# mcu_v041.net
KiCad netlist of a schematic drawn in EAGLE
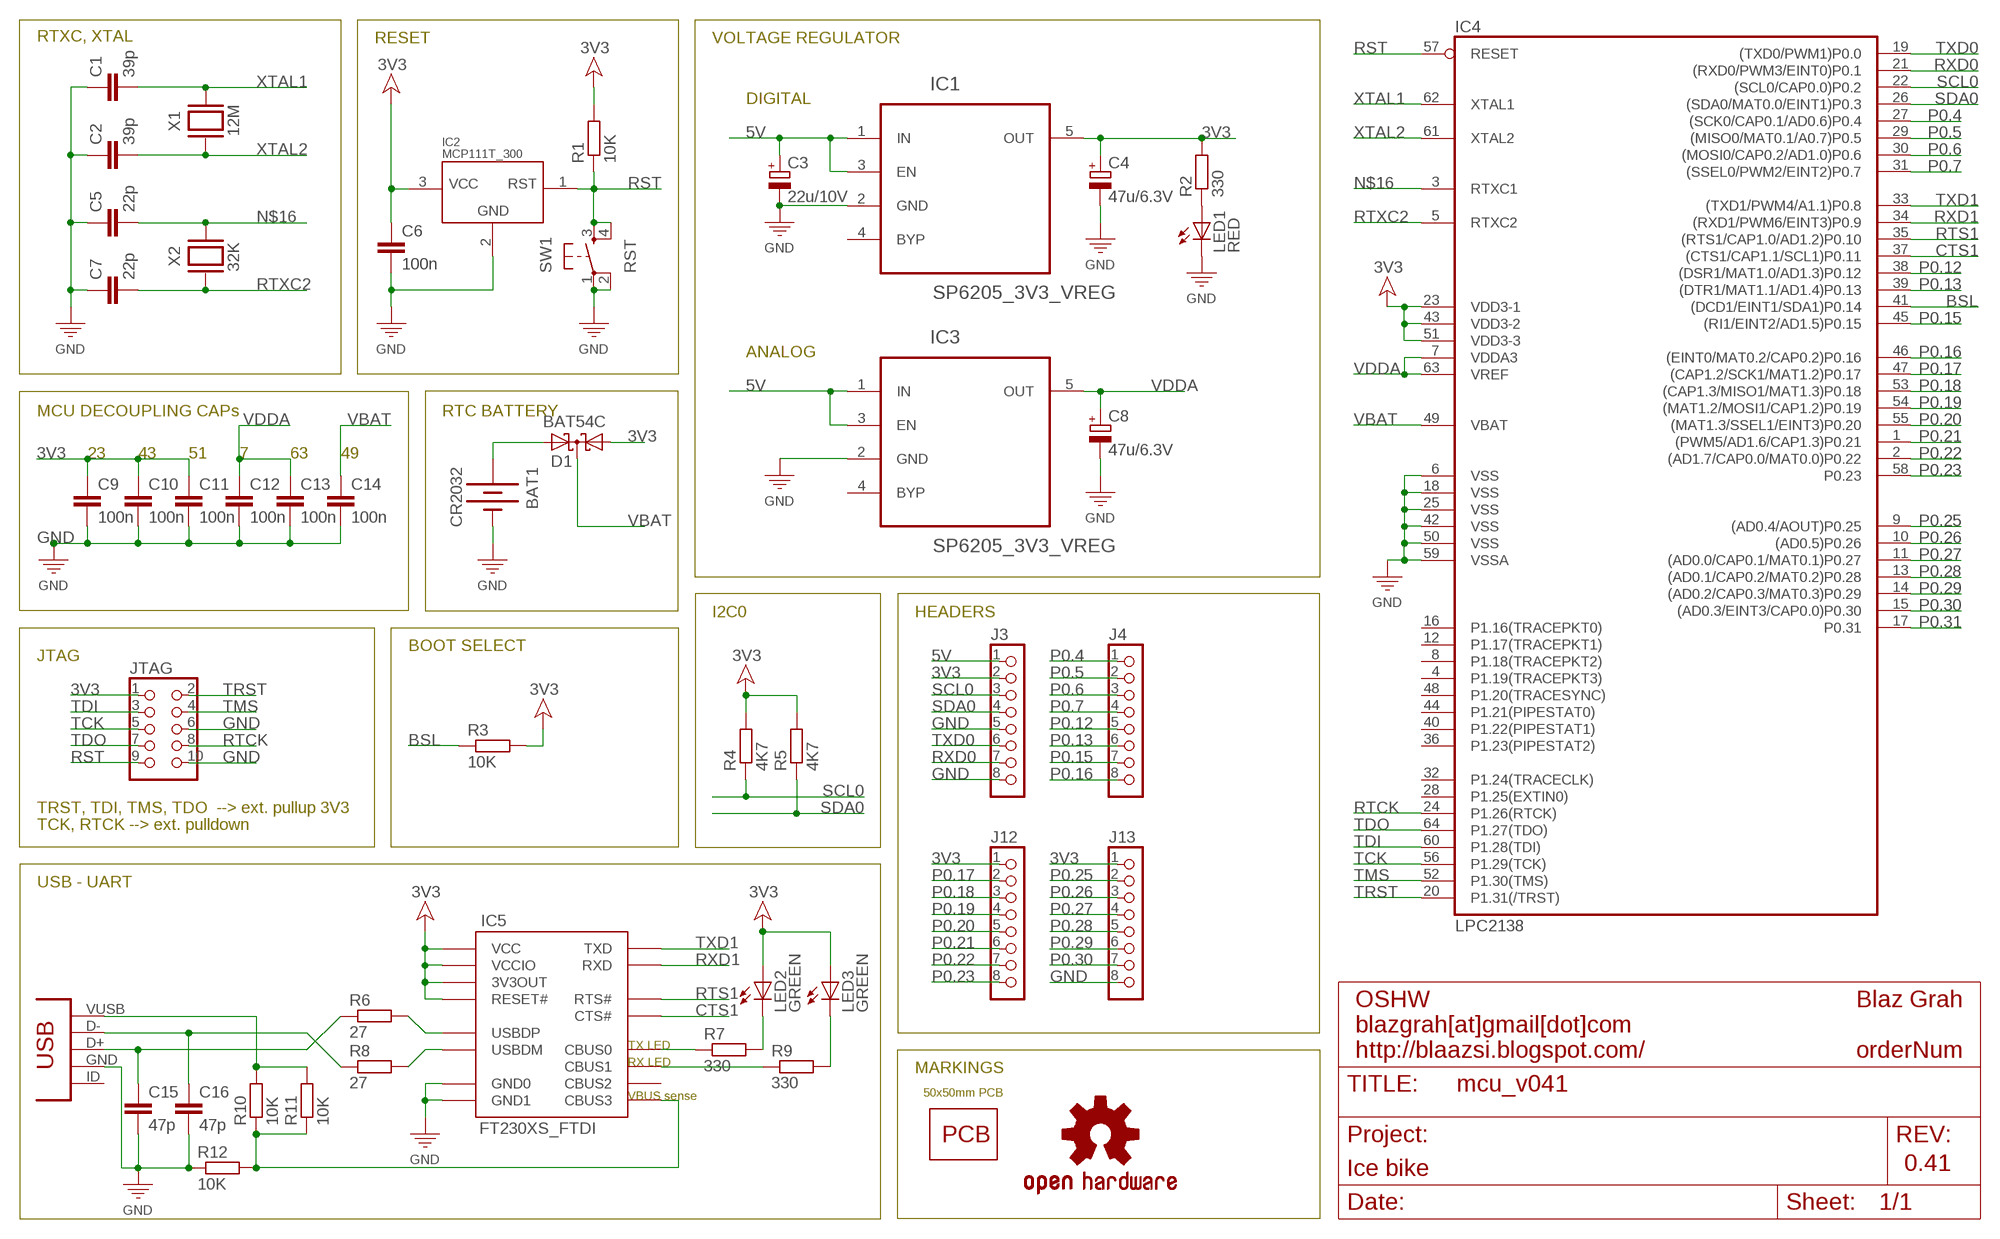
[diagram p0: schematic, sheet 1]

(export (version "E")
  (design (tool "Eeschema 10.0.6"))
  (components
    (comp (ref "BAT1")
      (value "CR2032")
      (footprint "eagle-import:BATTERY_20MM_SMD")
      (libsource (lib "eagle-import") (part "BATTERY20MM"))
    )
    (comp (ref "C1")
      (value "39p")
      (footprint "eagle-import:C0603")
      (libsource (lib "eagle-import") (part "C-EUC0603"))
    )
    (comp (ref "C2")
      (value "39p")
      (footprint "eagle-import:C0603")
      (libsource (lib "eagle-import") (part "C-EUC0603"))
    )
    (comp (ref "C3")
      (value "22u/10V")
      (footprint "eagle-import:SMC_B")
      (libsource (lib "eagle-import") (part "CAPACITOR_POL-SMC_B"))
    )
    (comp (ref "C4")
      (value "47u/6.3V")
      (footprint "eagle-import:SMC_B")
      (libsource (lib "eagle-import") (part "CAPACITOR_POL-SMC_B"))
    )
    (comp (ref "C5")
      (value "22p")
      (footprint "eagle-import:C0603")
      (libsource (lib "eagle-import") (part "C-EUC0603"))
    )
    (comp (ref "C6")
      (value "100n")
      (footprint "eagle-import:C0603")
      (libsource (lib "eagle-import") (part "C-EUC0603"))
    )
    (comp (ref "C7")
      (value "22p")
      (footprint "eagle-import:C0603")
      (libsource (lib "eagle-import") (part "C-EUC0603"))
    )
    (comp (ref "C8")
      (value "47u/6.3V")
      (footprint "eagle-import:SMC_B")
      (libsource (lib "eagle-import") (part "CAPACITOR_POL-SMC_B"))
    )
    (comp (ref "C9")
      (value "100n")
      (footprint "eagle-import:C0603")
      (libsource (lib "eagle-import") (part "C-EUC0603"))
    )
    (comp (ref "C10")
      (value "100n")
      (footprint "eagle-import:C0603")
      (libsource (lib "eagle-import") (part "C-EUC0603"))
    )
    (comp (ref "C11")
      (value "100n")
      (footprint "eagle-import:C0603")
      (libsource (lib "eagle-import") (part "C-EUC0603"))
    )
    (comp (ref "C12")
      (value "100n")
      (footprint "eagle-import:C0603")
      (libsource (lib "eagle-import") (part "C-EUC0603"))
    )
    (comp (ref "C13")
      (value "100n")
      (footprint "eagle-import:C0603")
      (libsource (lib "eagle-import") (part "C-EUC0603"))
    )
    (comp (ref "C14")
      (value "100n")
      (footprint "eagle-import:C0603")
      (libsource (lib "eagle-import") (part "C-EUC0603"))
    )
    (comp (ref "C15")
      (value "47p")
      (footprint "eagle-import:C0603")
      (libsource (lib "eagle-import") (part "C-EUC0603"))
    )
    (comp (ref "C16")
      (value "47p")
      (footprint "eagle-import:C0603")
      (libsource (lib "eagle-import") (part "C-EUC0603"))
    )
    (comp (ref "D1")
      (value "BAT54C")
      (footprint "eagle-import:SOT23")
      (libsource (lib "eagle-import") (part "BAT54C"))
    )
    (comp (ref "DOC")
      (value "FRAME_DINA4_L")
      (footprint "eagle-import:DP_LOGO")
      (fields
        (field (name "AUTHOR") "Blaz Grah")
        (field (name "LICENSE") "OSHW")
        (field (name "PROJECT") "Ice bike")
        (field (name "REV") "0.41")
        (field (name "URL1") "blazgrah[at]gmail[dot]com")
        (field (name "URL2") "http://blaazsi.blogspot.com/")
      )
      (libsource (lib "eagle-import") (part "FRAME_DINA4_L"))
    )
    (comp (ref "IC1")
      (value "SP6205_3V3_VREG")
      (footprint "eagle-import:SOT23-5")
      (libsource (lib "eagle-import") (part "SP6205_3V3_VREG"))
    )
    (comp (ref "IC2")
      (value "MCP111T_300")
      (footprint "eagle-import:SOT23")
      (libsource (lib "eagle-import") (part "MCP111T_300"))
    )
    (comp (ref "IC3")
      (value "SP6205_3V3_VREG")
      (footprint "eagle-import:SOT23-5")
      (libsource (lib "eagle-import") (part "SP6205_3V3_VREG"))
    )
    (comp (ref "IC4")
      (value "LPC2138")
      (footprint "eagle-import:LQFP64")
      (libsource (lib "eagle-import") (part "LCP2138_LQFP64"))
    )
    (comp (ref "IC5")
      (value "FT230XS_FTDI")
      (footprint "eagle-import:SSOP16")
      (libsource (lib "eagle-import") (part "FT230XS_FTDI"))
    )
    (comp (ref "J3")
      (value "CON_HEADER_1X08-PTH")
      (footprint "eagle-import:M1X8")
      (libsource (lib "eagle-import") (part "CON_HEADER_1X08-PTH"))
    )
    (comp (ref "J4")
      (value "CON_HEADER_1X08-PTH")
      (footprint "eagle-import:M1X8")
      (libsource (lib "eagle-import") (part "CON_HEADER_1X08-PTH"))
    )
    (comp (ref "J12")
      (value "CON_HEADER_1X08-PTH")
      (footprint "eagle-import:M1X8")
      (libsource (lib "eagle-import") (part "CON_HEADER_1X08-PTH"))
    )
    (comp (ref "J13")
      (value "CON_HEADER_1X08-PTH")
      (footprint "eagle-import:M1X8")
      (libsource (lib "eagle-import") (part "CON_HEADER_1X08-PTH"))
    )
    (comp (ref "JTAG")
      (value "CON_HEADER_2X05-PTH+SHROUDED_A")
      (footprint "eagle-import:PINSHRD_PTH_2X05")
      (libsource (lib "eagle-import") (part "CON_HEADER_2X05-PTH+SHROUDED_A"))
    )
    (comp (ref "LED1")
      (value "RED")
      (footprint "eagle-import:LED0805")
      (libsource (lib "eagle-import") (part "LED0805"))
    )
    (comp (ref "LED2")
      (value "GREEN")
      (footprint "eagle-import:LED0805")
      (libsource (lib "eagle-import") (part "LED0805"))
    )
    (comp (ref "LED3")
      (value "GREEN")
      (footprint "eagle-import:LED0805")
      (libsource (lib "eagle-import") (part "LED0805"))
    )
    (comp (ref "LOGO1")
      (value "OSHW-LOGOS")
      (footprint "eagle-import:OSHW-LOGO-S")
      (libsource (lib "eagle-import") (part "OSHW-LOGOS"))
    )
    (comp (ref "PCB1")
      (value "PCB")
      (footprint "eagle-import:PCB_50X50")
      (libsource (lib "eagle-import") (part "PCB"))
    )
    (comp (ref "R1")
      (value "10K")
      (footprint "eagle-import:R0603")
      (libsource (lib "eagle-import") (part "R-EU0603"))
    )
    (comp (ref "R2")
      (value "330")
      (footprint "eagle-import:R0603")
      (libsource (lib "eagle-import") (part "R-EU0603"))
    )
    (comp (ref "R3")
      (value "10K")
      (footprint "eagle-import:R0603")
      (libsource (lib "eagle-import") (part "R-EU0603"))
    )
    (comp (ref "R4")
      (value "4K7")
      (footprint "eagle-import:R0603")
      (libsource (lib "eagle-import") (part "R-EU0603"))
    )
    (comp (ref "R5")
      (value "4K7")
      (footprint "eagle-import:R0603")
      (libsource (lib "eagle-import") (part "R-EU0603"))
    )
    (comp (ref "R6")
      (value "27")
      (footprint "eagle-import:R0603")
      (libsource (lib "eagle-import") (part "R-EU0603"))
    )
    (comp (ref "R7")
      (value "330")
      (footprint "eagle-import:R0603")
      (libsource (lib "eagle-import") (part "R-EU0603"))
    )
    (comp (ref "R8")
      (value "27")
      (footprint "eagle-import:R0603")
      (libsource (lib "eagle-import") (part "R-EU0603"))
    )
    (comp (ref "R9")
      (value "330")
      (footprint "eagle-import:R0603")
      (libsource (lib "eagle-import") (part "R-EU0603"))
    )
    (comp (ref "R10")
      (value "10K")
      (footprint "eagle-import:R0603")
      (libsource (lib "eagle-import") (part "R-EU0603"))
    )
    (comp (ref "R11")
      (value "10K")
      (footprint "eagle-import:R0603")
      (libsource (lib "eagle-import") (part "R-EU0603"))
    )
    (comp (ref "R12")
      (value "10K")
      (footprint "eagle-import:R0603")
      (libsource (lib "eagle-import") (part "R-EU0603"))
    )
    (comp (ref "SW1")
      (value "RST")
      (footprint "eagle-import:BUTTON_SW_4P_SMD")
      (libsource (lib "eagle-import") (part "TACTIL_BUTTON"))
    )
    (comp (ref "USB1")
      (value "CON-USB-F-MINI-B")
      (footprint "eagle-import:CONN_USB_MINI-B")
      (libsource (lib "eagle-import") (part "CON-USB-F-MINI-B"))
    )
    (comp (ref "X1")
      (value "12M")
      (footprint "eagle-import:CRYSTAL_12M_4.8X10.6MM")
      (libsource (lib "eagle-import") (part "CRYSTALSMD_4.8X10.6"))
    )
    (comp (ref "X2")
      (value "32K")
      (footprint "eagle-import:CRYSTAL_32K_SMD")
      (libsource (lib "eagle-import") (part "CRYSTALSMD_32K"))
    )
  )
  (nets
    (net (code "1") (name "/5V") (class "Default")
      (node (ref "C3") (pin "+") (pinfunction "+_+") (pintype "passive"))
      (node (ref "IC1") (pin "1") (pinfunction "IN_1") (pintype "input"))
      (node (ref "IC1") (pin "3") (pinfunction "EN_3") (pintype "input"))
      (node (ref "IC3") (pin "1") (pinfunction "IN_1") (pintype "input"))
      (node (ref "IC3") (pin "3") (pinfunction "EN_3") (pintype "input"))
      (node (ref "J3") (pin "1") (pinfunction "1_1") (pintype "passive"))
    )
    (net (code "2") (name "/BSL") (class "Default")
      (node (ref "IC4") (pin "41") (pinfunction "(DCD1/EINT1/SDA1)P0.14_41") (pintype "bidirectional"))
      (node (ref "R3") (pin "1") (pinfunction "1_1") (pintype "passive"))
    )
    (net (code "3") (name "/CTS1") (class "Default")
      (node (ref "IC4") (pin "37") (pinfunction "(CTS1/CAP1.1/SCL1)P0.11_37") (pintype "bidirectional"))
      (node (ref "IC5") (pin "P$6") (pinfunction "CTS#_P$6") (pintype "bidirectional"))
    )
    (net (code "4") (name "/N$16") (class "Default")
      (node (ref "C5") (pin "2") (pinfunction "2_2") (pintype "passive"))
      (node (ref "IC4") (pin "3") (pinfunction "RTXC1_3") (pintype "input"))
      (node (ref "X2") (pin "X2") (pinfunction "2_X2") (pintype "passive"))
    )
    (net (code "5") (name "/P0.4") (class "Default")
      (node (ref "IC4") (pin "27") (pinfunction "(SCK0/CAP0.1/AD0.6)P0.4_27") (pintype "bidirectional"))
      (node (ref "J4") (pin "1") (pinfunction "1_1") (pintype "passive"))
    )
    (net (code "6") (name "/P0.5") (class "Default")
      (node (ref "IC4") (pin "29") (pinfunction "(MISO0/MAT0.1/A0.7)P0.5_29") (pintype "bidirectional"))
      (node (ref "J4") (pin "2") (pinfunction "2_2") (pintype "passive"))
    )
    (net (code "7") (name "/P0.6") (class "Default")
      (node (ref "IC4") (pin "30") (pinfunction "(MOSI0/CAP0.2/AD1.0)P0.6_30") (pintype "bidirectional"))
      (node (ref "J4") (pin "3") (pinfunction "3_3") (pintype "passive"))
    )
    (net (code "8") (name "/P0.7") (class "Default")
      (node (ref "IC4") (pin "31") (pinfunction "(SSEL0/PWM2/EINT2)P0.7_31") (pintype "bidirectional"))
      (node (ref "J4") (pin "4") (pinfunction "4_4") (pintype "passive"))
    )
    (net (code "9") (name "/P0.12") (class "Default")
      (node (ref "IC4") (pin "38") (pinfunction "(DSR1/MAT1.0/AD1.3)P0.12_38") (pintype "bidirectional"))
      (node (ref "J4") (pin "5") (pinfunction "5_5") (pintype "passive"))
    )
    (net (code "10") (name "/P0.13") (class "Default")
      (node (ref "IC4") (pin "39") (pinfunction "(DTR1/MAT1.1/AD1.4)P0.13_39") (pintype "bidirectional"))
      (node (ref "J4") (pin "6") (pinfunction "6_6") (pintype "passive"))
    )
    (net (code "11") (name "/P0.15") (class "Default")
      (node (ref "IC4") (pin "45") (pinfunction "(RI1/EINT2/AD1.5)P0.15_45") (pintype "bidirectional"))
      (node (ref "J4") (pin "7") (pinfunction "7_7") (pintype "passive"))
    )
    (net (code "12") (name "/P0.16") (class "Default")
      (node (ref "IC4") (pin "46") (pinfunction "(EINT0/MAT0.2/CAP0.2)P0.16_46") (pintype "bidirectional"))
      (node (ref "J4") (pin "8") (pinfunction "8_8") (pintype "passive"))
    )
    (net (code "13") (name "/P0.17") (class "Default")
      (node (ref "IC4") (pin "47") (pinfunction "(CAP1.2/SCK1/MAT1.2)P0.17_47") (pintype "bidirectional"))
      (node (ref "J12") (pin "2") (pinfunction "2_2") (pintype "passive"))
    )
    (net (code "14") (name "/P0.18") (class "Default")
      (node (ref "IC4") (pin "53") (pinfunction "(CAP1.3/MISO1/MAT1.3)P0.18_53") (pintype "bidirectional"))
      (node (ref "J12") (pin "3") (pinfunction "3_3") (pintype "passive"))
    )
    (net (code "15") (name "/P0.19") (class "Default")
      (node (ref "IC4") (pin "54") (pinfunction "(MAT1.2/MOSI1/CAP1.2)P0.19_54") (pintype "bidirectional"))
      (node (ref "J12") (pin "4") (pinfunction "4_4") (pintype "passive"))
    )
    (net (code "16") (name "/P0.20") (class "Default")
      (node (ref "IC4") (pin "55") (pinfunction "(MAT1.3/SSEL1/EINT3)P0.20_55") (pintype "bidirectional"))
      (node (ref "J12") (pin "5") (pinfunction "5_5") (pintype "passive"))
    )
    (net (code "17") (name "/P0.21") (class "Default")
      (node (ref "IC4") (pin "1") (pinfunction "(PWM5/AD1.6/CAP1.3)P0.21_1") (pintype "bidirectional"))
      (node (ref "J12") (pin "6") (pinfunction "6_6") (pintype "passive"))
    )
    (net (code "18") (name "/P0.22") (class "Default")
      (node (ref "IC4") (pin "2") (pinfunction "(AD1.7/CAP0.0/MAT0.0)P0.22_2") (pintype "bidirectional"))
      (node (ref "J12") (pin "7") (pinfunction "7_7") (pintype "passive"))
    )
    (net (code "19") (name "/P0.23") (class "Default")
      (node (ref "IC4") (pin "58") (pinfunction "P0.23_58") (pintype "bidirectional"))
      (node (ref "J12") (pin "8") (pinfunction "8_8") (pintype "passive"))
    )
    (net (code "20") (name "/P0.25") (class "Default")
      (node (ref "IC4") (pin "9") (pinfunction "(AD0.4/AOUT)P0.25_9") (pintype "bidirectional"))
      (node (ref "J13") (pin "2") (pinfunction "2_2") (pintype "passive"))
    )
    (net (code "21") (name "/P0.26") (class "Default")
      (node (ref "IC4") (pin "10") (pinfunction "(AD0.5)P0.26_10") (pintype "bidirectional"))
      (node (ref "J13") (pin "3") (pinfunction "3_3") (pintype "passive"))
    )
    (net (code "22") (name "/P0.27") (class "Default")
      (node (ref "IC4") (pin "11") (pinfunction "(AD0.0/CAP0.1/MAT0.1)P0.27_11") (pintype "bidirectional"))
      (node (ref "J13") (pin "4") (pinfunction "4_4") (pintype "passive"))
    )
    (net (code "23") (name "/P0.28") (class "Default")
      (node (ref "IC4") (pin "13") (pinfunction "(AD0.1/CAP0.2/MAT0.2)P0.28_13") (pintype "bidirectional"))
      (node (ref "J13") (pin "5") (pinfunction "5_5") (pintype "passive"))
    )
    (net (code "24") (name "/P0.29") (class "Default")
      (node (ref "IC4") (pin "14") (pinfunction "(AD0.2/CAP0.3/MAT0.3)P0.29_14") (pintype "bidirectional"))
      (node (ref "J13") (pin "6") (pinfunction "6_6") (pintype "passive"))
    )
    (net (code "25") (name "/P0.30") (class "Default")
      (node (ref "IC4") (pin "15") (pinfunction "(AD0.3/EINT3/CAP0.0)P0.30_15") (pintype "bidirectional"))
      (node (ref "J13") (pin "7") (pinfunction "7_7") (pintype "passive"))
    )
    (net (code "26") (name "/P0.31") (class "Default")
      (node (ref "IC4") (pin "17") (pinfunction "P0.31_17") (pintype "output"))
    )
    (net (code "27") (name "/RST") (class "Default")
      (node (ref "IC2") (pin "1") (pinfunction "RST_1") (pintype "output"))
      (node (ref "IC4") (pin "57") (pinfunction "RESET_57") (pintype "input"))
      (node (ref "JTAG") (pin "9") (pinfunction "9_9") (pintype "passive"))
      (node (ref "R1") (pin "1") (pinfunction "1_1") (pintype "passive"))
      (node (ref "SW1") (pin "3") (pinfunction "3_3") (pintype "passive"))
      (node (ref "SW1") (pin "4") (pinfunction "4_4") (pintype "passive"))
    )
    (net (code "28") (name "/RTCK") (class "Default")
      (node (ref "IC4") (pin "24") (pinfunction "P1.26(RTCK)_24") (pintype "bidirectional"))
      (node (ref "JTAG") (pin "8") (pinfunction "8_8") (pintype "passive"))
    )
    (net (code "29") (name "/RTS1") (class "Default")
      (node (ref "IC4") (pin "35") (pinfunction "(RTS1/CAP1.0/AD1.2)P0.10_35") (pintype "bidirectional"))
      (node (ref "IC5") (pin "P$2") (pinfunction "RTS#_P$2") (pintype "bidirectional"))
    )
    (net (code "30") (name "/RTXC2") (class "Default")
      (node (ref "C7") (pin "2") (pinfunction "2_2") (pintype "passive"))
      (node (ref "IC4") (pin "5") (pinfunction "RTXC2_5") (pintype "output"))
      (node (ref "X2") (pin "X1") (pinfunction "1_X1") (pintype "passive"))
    )
    (net (code "31") (name "/RXD0") (class "Default")
      (node (ref "IC4") (pin "21") (pinfunction "(RXD0/PWM3/EINT0)P0.1_21") (pintype "bidirectional"))
      (node (ref "J3") (pin "7") (pinfunction "7_7") (pintype "passive"))
    )
    (net (code "32") (name "/RXD1") (class "Default")
      (node (ref "IC4") (pin "34") (pinfunction "(RXD1/PWM6/EINT3)P0.9_34") (pintype "bidirectional"))
      (node (ref "IC5") (pin "P$4") (pinfunction "RXD_P$4") (pintype "bidirectional"))
    )
    (net (code "33") (name "/SCL0") (class "Default")
      (node (ref "IC4") (pin "22") (pinfunction "(SCL0/CAP0.0)P0.2_22") (pintype "bidirectional"))
      (node (ref "J3") (pin "3") (pinfunction "3_3") (pintype "passive"))
      (node (ref "R4") (pin "1") (pinfunction "1_1") (pintype "passive"))
    )
    (net (code "34") (name "/SDA0") (class "Default")
      (node (ref "IC4") (pin "26") (pinfunction "(SDA0/MAT0.0/EINT1)P0.3_26") (pintype "bidirectional"))
      (node (ref "J3") (pin "4") (pinfunction "4_4") (pintype "passive"))
      (node (ref "R5") (pin "1") (pinfunction "1_1") (pintype "passive"))
    )
    (net (code "35") (name "/TCK") (class "Default")
      (node (ref "IC4") (pin "56") (pinfunction "P1.29(TCK)_56") (pintype "bidirectional"))
      (node (ref "JTAG") (pin "5") (pinfunction "5_5") (pintype "passive"))
    )
    (net (code "36") (name "/TDI") (class "Default")
      (node (ref "IC4") (pin "60") (pinfunction "P1.28(TDI)_60") (pintype "bidirectional"))
      (node (ref "JTAG") (pin "3") (pinfunction "3_3") (pintype "passive"))
    )
    (net (code "37") (name "/TDO") (class "Default")
      (node (ref "IC4") (pin "64") (pinfunction "P1.27(TDO)_64") (pintype "bidirectional"))
      (node (ref "JTAG") (pin "7") (pinfunction "7_7") (pintype "passive"))
    )
    (net (code "38") (name "/TMS") (class "Default")
      (node (ref "IC4") (pin "52") (pinfunction "P1.30(TMS)_52") (pintype "bidirectional"))
      (node (ref "JTAG") (pin "4") (pinfunction "4_4") (pintype "passive"))
    )
    (net (code "39") (name "/TRST") (class "Default")
      (node (ref "IC4") (pin "20") (pinfunction "P1.31(/TRST)_20") (pintype "bidirectional"))
      (node (ref "JTAG") (pin "2") (pinfunction "2_2") (pintype "passive"))
    )
    (net (code "40") (name "/TXD0") (class "Default")
      (node (ref "IC4") (pin "19") (pinfunction "(TXD0/PWM1)P0.0_19") (pintype "bidirectional"))
      (node (ref "J3") (pin "6") (pinfunction "6_6") (pintype "passive"))
    )
    (net (code "41") (name "/TXD1") (class "Default")
      (node (ref "IC4") (pin "33") (pinfunction "(TXD1/PWM4/A1.1)P0.8_33") (pintype "bidirectional"))
      (node (ref "IC5") (pin "P$1") (pinfunction "TXD_P$1") (pintype "bidirectional"))
    )
    (net (code "42") (name "/VBAT") (class "Default")
      (node (ref "C14") (pin "1") (pinfunction "1_1") (pintype "passive"))
      (node (ref "D1") (pin "3") (pinfunction "CC_3") (pintype "passive"))
      (node (ref "IC4") (pin "49") (pinfunction "VBAT_49") (pintype "power_in"))
    )
    (net (code "43") (name "/VDDA") (class "Default")
      (node (ref "C12") (pin "1") (pinfunction "1_1") (pintype "passive"))
      (node (ref "C13") (pin "1") (pinfunction "1_1") (pintype "passive"))
      (node (ref "C8") (pin "+") (pinfunction "+_+") (pintype "passive"))
      (node (ref "IC3") (pin "5") (pinfunction "OUT_5") (pintype "power_in"))
      (node (ref "IC4") (pin "63") (pinfunction "VREF_63") (pintype "input"))
      (node (ref "IC4") (pin "7") (pinfunction "VDDA3_7") (pintype "power_in"))
    )
    (net (code "44") (name "/XTAL1") (class "Default")
      (node (ref "C1") (pin "2") (pinfunction "2_2") (pintype "passive"))
      (node (ref "IC4") (pin "62") (pinfunction "XTAL1_62") (pintype "input"))
      (node (ref "X1") (pin "P$2") (pinfunction "2_P$2") (pintype "passive"))
    )
    (net (code "45") (name "/XTAL2") (class "Default")
      (node (ref "C2") (pin "2") (pinfunction "2_2") (pintype "passive"))
      (node (ref "IC4") (pin "61") (pinfunction "XTAL2_61") (pintype "output"))
      (node (ref "X1") (pin "P$1") (pinfunction "1_P$1") (pintype "passive"))
    )
    (net (code "46") (name "3V3") (class "Default")
      (node (ref "C10") (pin "1") (pinfunction "1_1") (pintype "passive"))
      (node (ref "C11") (pin "1") (pinfunction "1_1") (pintype "passive"))
      (node (ref "C4") (pin "+") (pinfunction "+_+") (pintype "passive"))
      (node (ref "C6") (pin "1") (pinfunction "1_1") (pintype "passive"))
      (node (ref "C9") (pin "1") (pinfunction "1_1") (pintype "passive"))
      (node (ref "D1") (pin "1") (pinfunction "A1_1") (pintype "passive"))
      (node (ref "IC1") (pin "5") (pinfunction "OUT_5") (pintype "power_in"))
      (node (ref "IC2") (pin "3") (pinfunction "VCC_3") (pintype "input"))
      (node (ref "IC4") (pin "23") (pinfunction "VDD3-1_23") (pintype "power_in"))
      (node (ref "IC4") (pin "43") (pinfunction "VDD3-2_43") (pintype "power_in"))
      (node (ref "IC4") (pin "51") (pinfunction "VDD3-3_51") (pintype "power_in"))
      (node (ref "IC5") (pin "P$10") (pinfunction "3V3OUT_P$10") (pintype "power_in"))
      (node (ref "IC5") (pin "P$11") (pinfunction "RESET#_P$11") (pintype "bidirectional"))
      (node (ref "IC5") (pin "P$12") (pinfunction "VCC_P$12") (pintype "power_in"))
      (node (ref "IC5") (pin "P$3") (pinfunction "VCCIO_P$3") (pintype "power_in"))
      (node (ref "J12") (pin "1") (pinfunction "1_1") (pintype "passive"))
      (node (ref "J13") (pin "1") (pinfunction "1_1") (pintype "passive"))
      (node (ref "J3") (pin "2") (pinfunction "2_2") (pintype "passive"))
      (node (ref "JTAG") (pin "1") (pinfunction "1_1") (pintype "passive"))
      (node (ref "LED2") (pin "A") (pinfunction "A_A") (pintype "passive"))
      (node (ref "LED3") (pin "A") (pinfunction "A_A") (pintype "passive"))
      (node (ref "R1") (pin "2") (pinfunction "2_2") (pintype "passive"))
      (node (ref "R2") (pin "2") (pinfunction "2_2") (pintype "passive"))
      (node (ref "R3") (pin "2") (pinfunction "2_2") (pintype "passive"))
      (node (ref "R4") (pin "2") (pinfunction "2_2") (pintype "passive"))
      (node (ref "R5") (pin "2") (pinfunction "2_2") (pintype "passive"))
    )
    (net (code "47") (name "GND") (class "Default")
      (node (ref "BAT1") (pin "NEG") (pinfunction "NEG_NEG") (pintype "power_in"))
      (node (ref "C1") (pin "1") (pinfunction "1_1") (pintype "passive"))
      (node (ref "C10") (pin "2") (pinfunction "2_2") (pintype "passive"))
      (node (ref "C11") (pin "2") (pinfunction "2_2") (pintype "passive"))
      (node (ref "C12") (pin "2") (pinfunction "2_2") (pintype "passive"))
      (node (ref "C13") (pin "2") (pinfunction "2_2") (pintype "passive"))
      (node (ref "C14") (pin "2") (pinfunction "2_2") (pintype "passive"))
      (node (ref "C15") (pin "2") (pinfunction "2_2") (pintype "passive"))
      (node (ref "C16") (pin "2") (pinfunction "2_2") (pintype "passive"))
      (node (ref "C2") (pin "1") (pinfunction "1_1") (pintype "passive"))
      (node (ref "C3") (pin "-") (pinfunction "-_-") (pintype "passive"))
      (node (ref "C4") (pin "-") (pinfunction "-_-") (pintype "passive"))
      (node (ref "C5") (pin "1") (pinfunction "1_1") (pintype "passive"))
      (node (ref "C6") (pin "2") (pinfunction "2_2") (pintype "passive"))
      (node (ref "C7") (pin "1") (pinfunction "1_1") (pintype "passive"))
      (node (ref "C8") (pin "-") (pinfunction "-_-") (pintype "passive"))
      (node (ref "C9") (pin "2") (pinfunction "2_2") (pintype "passive"))
      (node (ref "IC1") (pin "2") (pinfunction "GND_2") (pintype "power_in"))
      (node (ref "IC2") (pin "2") (pinfunction "GND_2") (pintype "power_in"))
      (node (ref "IC3") (pin "2") (pinfunction "GND_2") (pintype "power_in"))
      (node (ref "IC4") (pin "18") (pinfunction "VSS_18") (pintype "power_in"))
      (node (ref "IC4") (pin "25") (pinfunction "VSS_25") (pintype "power_in"))
      (node (ref "IC4") (pin "42") (pinfunction "VSS_42") (pintype "power_in"))
      (node (ref "IC4") (pin "50") (pinfunction "VSS_50") (pintype "power_in"))
      (node (ref "IC4") (pin "59") (pinfunction "VSSA_59") (pintype "power_in"))
      (node (ref "IC4") (pin "6") (pinfunction "VSS_6") (pintype "power_in"))
      (node (ref "IC5") (pin "P$13") (pinfunction "GND1_P$13") (pintype "power_in"))
      (node (ref "IC5") (pin "P$5") (pinfunction "GND0_P$5") (pintype "power_in"))
      (node (ref "J13") (pin "8") (pinfunction "8_8") (pintype "passive"))
      (node (ref "J3") (pin "5") (pinfunction "5_5") (pintype "passive"))
      (node (ref "J3") (pin "8") (pinfunction "8_8") (pintype "passive"))
      (node (ref "JTAG") (pin "10") (pinfunction "10_10") (pintype "passive"))
      (node (ref "JTAG") (pin "6") (pinfunction "6_6") (pintype "passive"))
      (node (ref "LED1") (pin "C") (pinfunction "C_C") (pintype "passive"))
      (node (ref "R12") (pin "1") (pinfunction "1_1") (pintype "passive"))
      (node (ref "SW1") (pin "1") (pinfunction "1_1") (pintype "passive"))
      (node (ref "SW1") (pin "2") (pinfunction "2_2") (pintype "passive"))
      (node (ref "USB1") (pin "GND") (pinfunction "GND_GND") (pintype "bidirectional"))
    )
    (net (code "48") (name "Net-(C15-Pad1)") (class "Default")
      (node (ref "C15") (pin "1") (pinfunction "1_1") (pintype "passive"))
      (node (ref "R6") (pin "1") (pinfunction "1_1") (pintype "passive"))
      (node (ref "USB1") (pin "D+") (pinfunction "D+_D+") (pintype "bidirectional"))
    )
    (net (code "49") (name "Net-(C16-Pad1)") (class "Default")
      (node (ref "C16") (pin "1") (pinfunction "1_1") (pintype "passive"))
      (node (ref "R8") (pin "1") (pinfunction "1_1") (pintype "passive"))
      (node (ref "USB1") (pin "D-") (pinfunction "D-_D-") (pintype "bidirectional"))
    )
    (net (code "50") (name "Net-(D1-A2)") (class "Default")
      (node (ref "BAT1") (pin "POS1") (pinfunction "POZ_POS1") (pintype "power_in"))
      (node (ref "BAT1") (pin "POS2") (pinfunction "POZ_POS2") (pintype "power_in"))
      (node (ref "D1") (pin "2") (pinfunction "A2_2") (pintype "passive"))
    )
    (net (code "51") (name "Net-(IC5-CBUS0)") (class "Default")
      (node (ref "IC5") (pin "P$15") (pinfunction "CBUS0_P$15") (pintype "bidirectional"))
      (node (ref "R7") (pin "1") (pinfunction "1_1") (pintype "passive"))
    )
    (net (code "52") (name "Net-(IC5-CBUS1)") (class "Default")
      (node (ref "IC5") (pin "P$14") (pinfunction "CBUS1_P$14") (pintype "bidirectional"))
      (node (ref "R9") (pin "1") (pinfunction "1_1") (pintype "passive"))
    )
    (net (code "53") (name "Net-(IC5-CBUS3)") (class "Default")
      (node (ref "IC5") (pin "P$16") (pinfunction "CBUS3_P$16") (pintype "bidirectional"))
      (node (ref "R10") (pin "1") (pinfunction "1_1") (pintype "passive"))
      (node (ref "R11") (pin "1") (pinfunction "1_1") (pintype "passive"))
      (node (ref "R12") (pin "2") (pinfunction "2_2") (pintype "passive"))
    )
    (net (code "54") (name "Net-(IC5-USBDM)") (class "Default")
      (node (ref "IC5") (pin "P$9") (pinfunction "USBDM_P$9") (pintype "bidirectional"))
      (node (ref "R8") (pin "2") (pinfunction "2_2") (pintype "passive"))
    )
    (net (code "55") (name "Net-(IC5-USBDP)") (class "Default")
      (node (ref "IC5") (pin "P$8") (pinfunction "USBDP_P$8") (pintype "bidirectional"))
      (node (ref "R6") (pin "2") (pinfunction "2_2") (pintype "passive"))
    )
    (net (code "56") (name "Net-(LED1-PadA)") (class "Default")
      (node (ref "LED1") (pin "A") (pinfunction "A_A") (pintype "passive"))
      (node (ref "R2") (pin "1") (pinfunction "1_1") (pintype "passive"))
    )
    (net (code "57") (name "Net-(LED2-PadC)") (class "Default")
      (node (ref "LED2") (pin "C") (pinfunction "C_C") (pintype "passive"))
      (node (ref "R7") (pin "2") (pinfunction "2_2") (pintype "passive"))
    )
    (net (code "58") (name "Net-(LED3-PadC)") (class "Default")
      (node (ref "LED3") (pin "C") (pinfunction "C_C") (pintype "passive"))
      (node (ref "R9") (pin "2") (pinfunction "2_2") (pintype "passive"))
    )
    (net (code "59") (name "Net-(R10-Pad2)") (class "Default")
      (node (ref "R10") (pin "2") (pinfunction "2_2") (pintype "passive"))
      (node (ref "R11") (pin "2") (pinfunction "2_2") (pintype "passive"))
      (node (ref "USB1") (pin "VUSB") (pinfunction "VUSB_VUSB") (pintype "bidirectional"))
    )
    (net (code "60") (name "unconnected-(IC1-BYP-Pad4)") (class "Default")
      (node (ref "IC1") (pin "4") (pinfunction "BYP_4") (pintype "no_connect"))
    )
    (net (code "61") (name "unconnected-(IC3-BYP-Pad4)") (class "Default")
      (node (ref "IC3") (pin "4") (pinfunction "BYP_4") (pintype "no_connect"))
    )
    (net (code "62") (name "unconnected-(IC4-P1.16(TRACEPKT0)-Pad16)") (class "Default")
      (node (ref "IC4") (pin "16") (pinfunction "P1.16(TRACEPKT0)_16") (pintype "bidirectional"))
    )
    (net (code "63") (name "unconnected-(IC4-P1.17(TRACEPKT1)-Pad12)") (class "Default")
      (node (ref "IC4") (pin "12") (pinfunction "P1.17(TRACEPKT1)_12") (pintype "bidirectional"))
    )
    (net (code "64") (name "unconnected-(IC4-P1.18(TRACEPKT2)-Pad8)") (class "Default")
      (node (ref "IC4") (pin "8") (pinfunction "P1.18(TRACEPKT2)_8") (pintype "bidirectional"))
    )
    (net (code "65") (name "unconnected-(IC4-P1.19(TRACEPKT3)-Pad4)") (class "Default")
      (node (ref "IC4") (pin "4") (pinfunction "P1.19(TRACEPKT3)_4") (pintype "bidirectional"))
    )
    (net (code "66") (name "unconnected-(IC4-P1.20(TRACESYNC)-Pad48)") (class "Default")
      (node (ref "IC4") (pin "48") (pinfunction "P1.20(TRACESYNC)_48") (pintype "bidirectional"))
    )
    (net (code "67") (name "unconnected-(IC4-P1.21(PIPESTAT0)-Pad44)") (class "Default")
      (node (ref "IC4") (pin "44") (pinfunction "P1.21(PIPESTAT0)_44") (pintype "bidirectional"))
    )
    (net (code "68") (name "unconnected-(IC4-P1.22(PIPESTAT1)-Pad40)") (class "Default")
      (node (ref "IC4") (pin "40") (pinfunction "P1.22(PIPESTAT1)_40") (pintype "bidirectional"))
    )
    (net (code "69") (name "unconnected-(IC4-P1.23(PIPESTAT2)-Pad36)") (class "Default")
      (node (ref "IC4") (pin "36") (pinfunction "P1.23(PIPESTAT2)_36") (pintype "bidirectional"))
    )
    (net (code "70") (name "unconnected-(IC4-P1.24(TRACECLK)-Pad32)") (class "Default")
      (node (ref "IC4") (pin "32") (pinfunction "P1.24(TRACECLK)_32") (pintype "bidirectional"))
    )
    (net (code "71") (name "unconnected-(IC4-P1.25(EXTIN0)-Pad28)") (class "Default")
      (node (ref "IC4") (pin "28") (pinfunction "P1.25(EXTIN0)_28") (pintype "bidirectional"))
    )
    (net (code "72") (name "unconnected-(IC5-CBUS2-PadP$7)") (class "Default")
      (node (ref "IC5") (pin "P$7") (pinfunction "CBUS2_P$7") (pintype "bidirectional"))
    )
    (net (code "73") (name "unconnected-(USB1B-USBID-PadID)") (class "Default")
      (node (ref "USB1") (pin "ID") (pinfunction "USBID_ID") (pintype "bidirectional"))
    )
  )
)
